# USBtoMIDI.net
KiCad netlist of a schematic drawn in EasyEDA
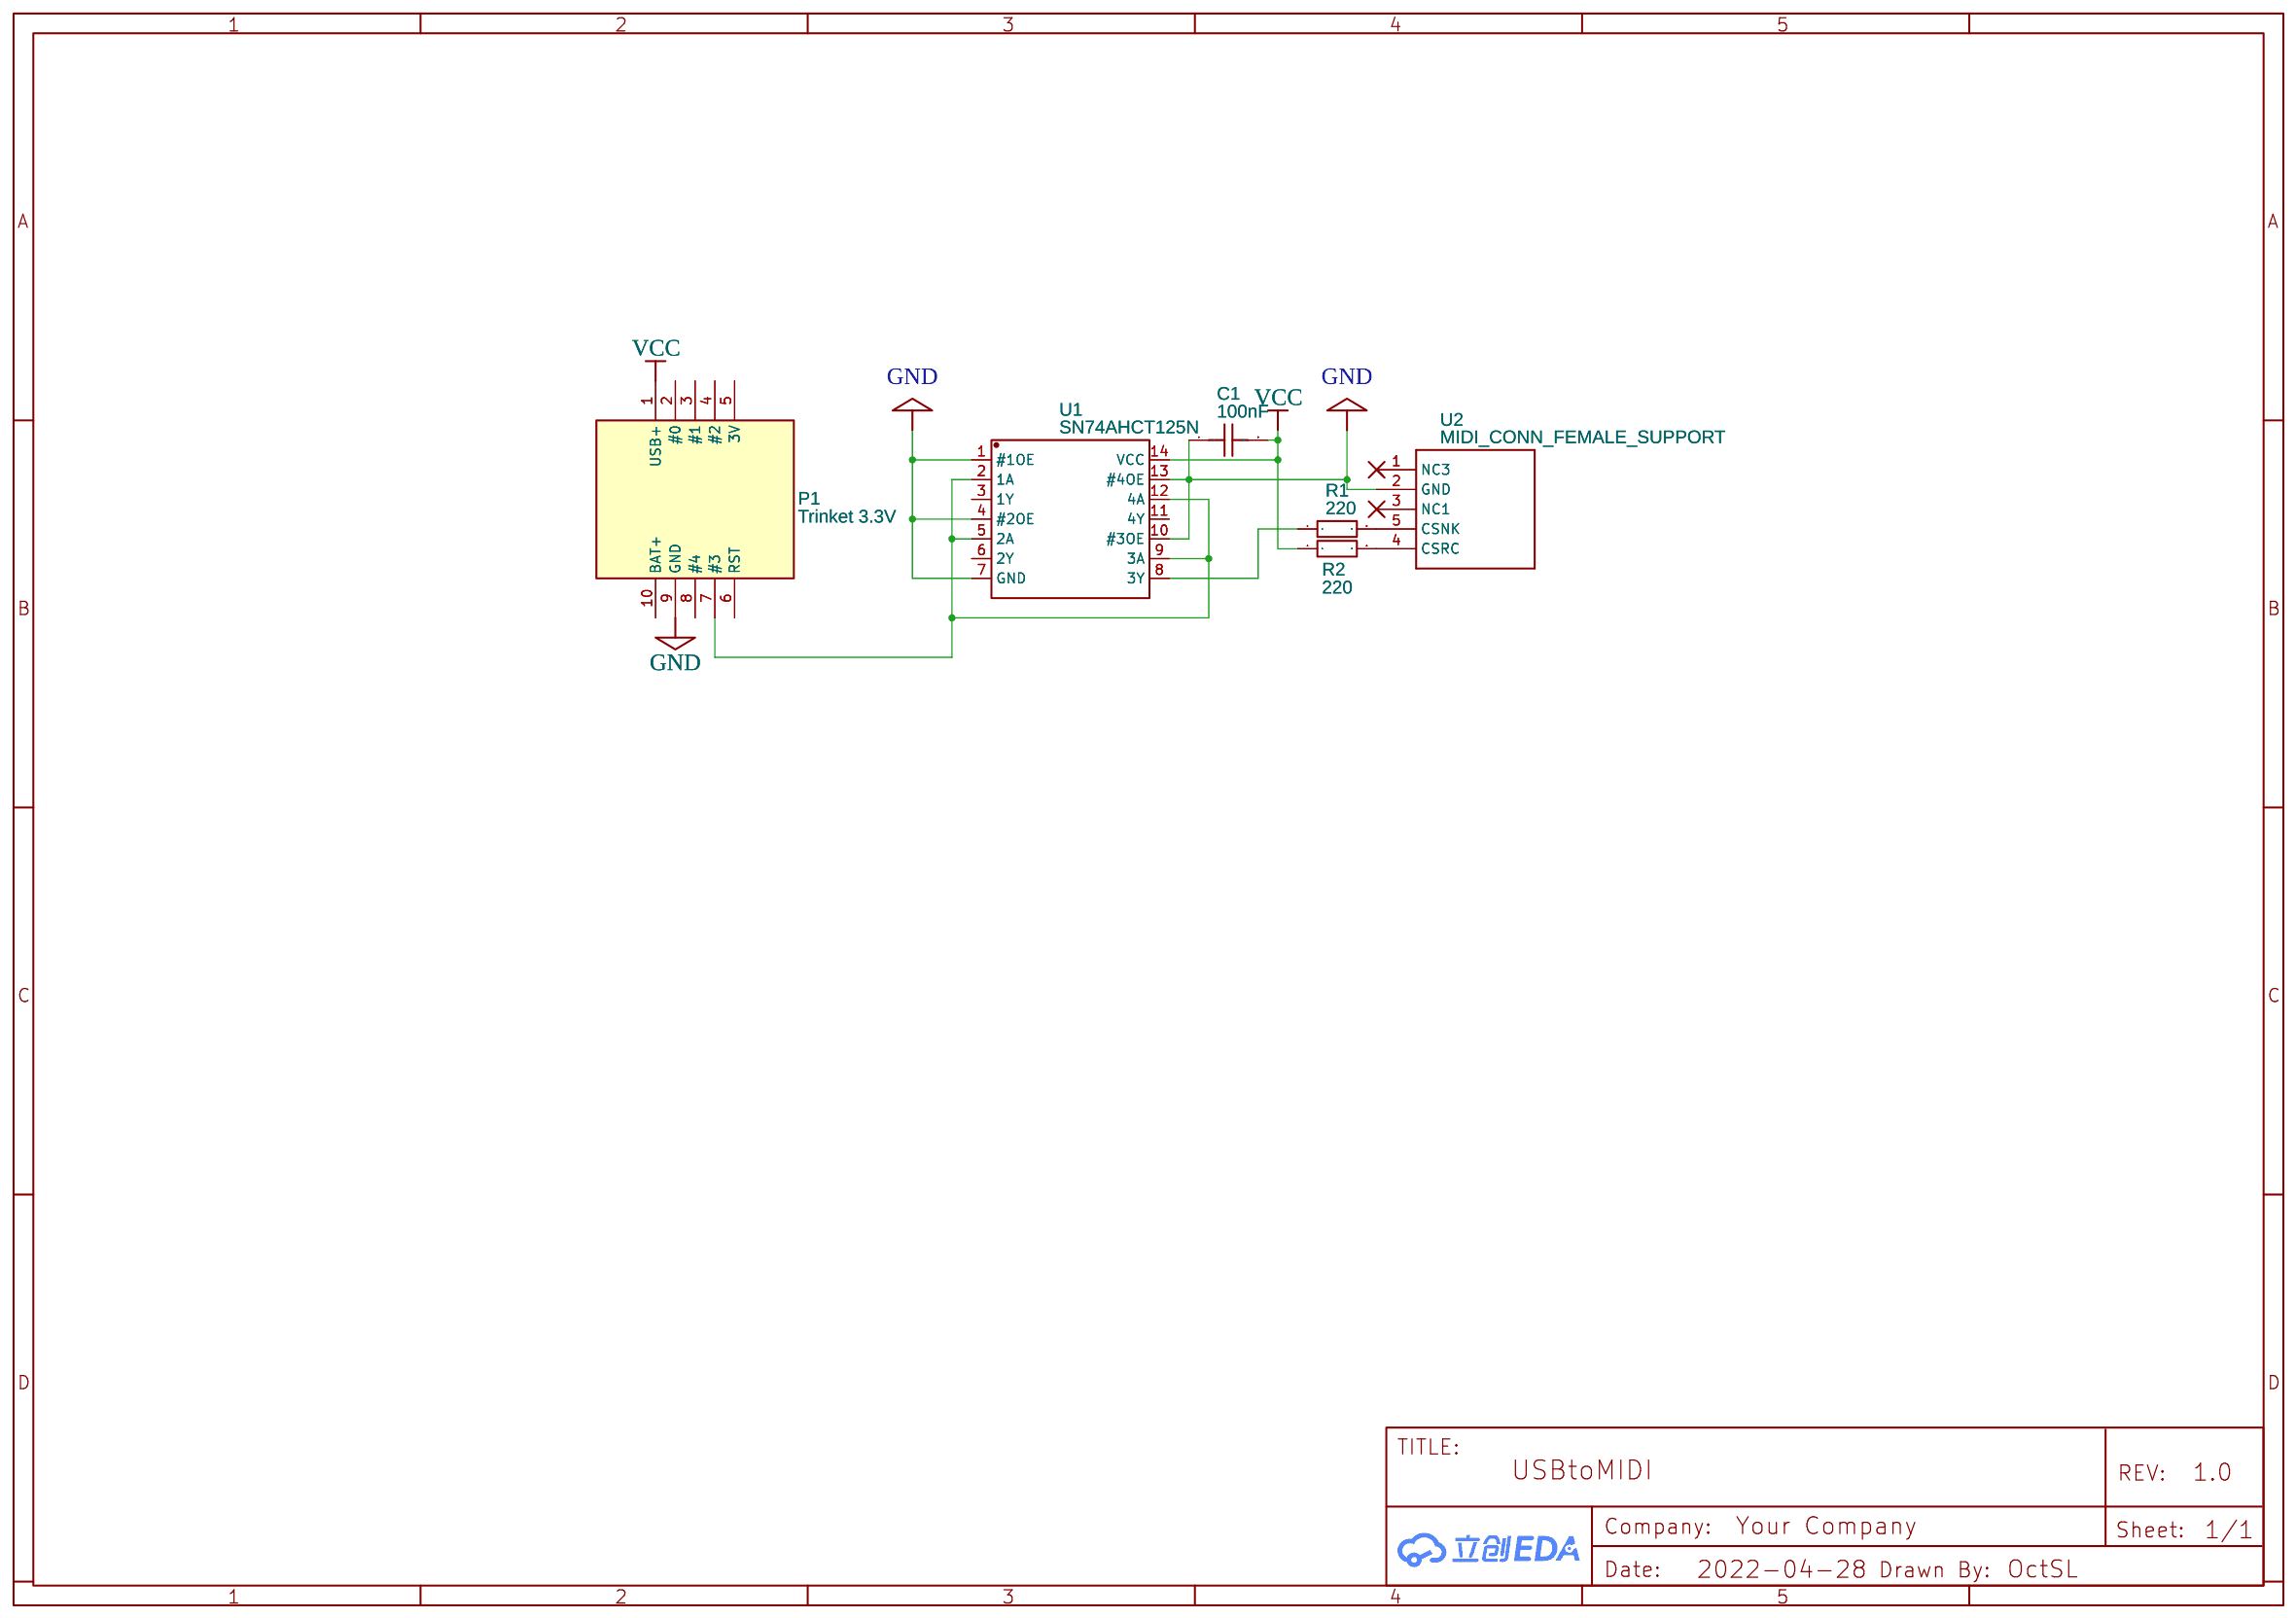
[diagram p0: schematic sheet]

(export (version "E")
  (design (tool "Eeschema 10.0.6"))
  (components
    (comp (ref "C1")
      (value "100nF")
      (fields
        (field (name "BOM_Manufacturer Part") "ACC-B104K500P")
        (field (name "BOM_Supplier Part") "C94703")
      )
      (libsource (lib "") (part "ACC-B104K500P"))
    )
    (comp (ref "P1") (value "Trinket 3.3V") (libsource (lib "") (part "Trinket 3.3V")))
    (comp (ref "R1")
      (value "220")
      (fields (field (name "BOM_Supplier Part") "C122180"))
      (libsource (lib "") (part "RI40-1/4W-1MΩ±5% T"))
    )
    (comp (ref "R2")
      (value "220")
      (fields (field (name "BOM_Supplier Part") "C122180"))
      (libsource (lib "") (part "RI40-1/4W-1MΩ±5% T"))
    )
    (comp (ref "U1")
      (value "SN74AHCT125N")
      (fields (field (name "BOM_Supplier Part") "C354152"))
      (libsource (lib "") (part "SN74AHCT125N"))
    )
    (comp (ref "U2")
      (value "MIDI_CONN_FEMALE_SUPPORT")
      (libsource (lib "") (part "MIDI_CONN_FEMALE_SUPPORT"))
    )
  )
  (nets
    (net (code "1") (name "GND") (class "Default")
      (node (ref "C1") (pin "1") (pinfunction "1_1") (pintype "unspecified"))
      (node (ref "P1") (pin "9") (pinfunction "GND_9") (pintype "unspecified"))
      (node (ref "U1") (pin "1") (pinfunction "#1OE_1") (pintype "unspecified"))
      (node (ref "U1") (pin "10") (pinfunction "#3OE_10") (pintype "unspecified"))
      (node (ref "U1") (pin "13") (pinfunction "#4OE_13") (pintype "unspecified"))
      (node (ref "U1") (pin "4") (pinfunction "#2OE_4") (pintype "unspecified"))
      (node (ref "U1") (pin "7") (pinfunction "GND_7") (pintype "unspecified"))
      (node (ref "U2") (pin "2") (pinfunction "GND_2") (pintype "unspecified"))
    )
    (net (code "2") (name "Net-(P1-#3)") (class "Default")
      (node (ref "P1") (pin "7") (pinfunction "#3_7") (pintype "unspecified"))
      (node (ref "U1") (pin "12") (pinfunction "4A_12") (pintype "unspecified"))
      (node (ref "U1") (pin "2") (pinfunction "1A_2") (pintype "unspecified"))
      (node (ref "U1") (pin "5") (pinfunction "2A_5") (pintype "unspecified"))
      (node (ref "U1") (pin "9") (pinfunction "3A_9") (pintype "unspecified"))
    )
    (net (code "3") (name "Net-(U1-3Y)") (class "Default")
      (node (ref "R1") (pin "1") (pinfunction "1_1") (pintype "unspecified"))
      (node (ref "U1") (pin "8") (pinfunction "3Y_8") (pintype "unspecified"))
    )
    (net (code "4") (name "Net-(U2-CSNK)") (class "Default")
      (node (ref "R1") (pin "2") (pinfunction "2_2") (pintype "unspecified"))
      (node (ref "U2") (pin "5") (pinfunction "CSNK_5") (pintype "unspecified"))
    )
    (net (code "5") (name "Net-(U2-CSRC)") (class "Default")
      (node (ref "R2") (pin "2") (pinfunction "2_2") (pintype "unspecified"))
      (node (ref "U2") (pin "4") (pinfunction "CSRC_4") (pintype "unspecified"))
    )
    (net (code "6") (name "VCC") (class "Default")
      (node (ref "C1") (pin "2") (pinfunction "2_2") (pintype "unspecified"))
      (node (ref "P1") (pin "1") (pinfunction "USB+_1") (pintype "unspecified"))
      (node (ref "R2") (pin "1") (pinfunction "1_1") (pintype "unspecified"))
      (node (ref "U1") (pin "14") (pinfunction "VCC_14") (pintype "unspecified"))
    )
    (net (code "7") (name "unconnected-(P1-#0-Pad2)") (class "Default")
      (node (ref "P1") (pin "2") (pinfunction "#0_2") (pintype "unspecified"))
    )
    (net (code "8") (name "unconnected-(P1-#1-Pad3)") (class "Default")
      (node (ref "P1") (pin "3") (pinfunction "#1_3") (pintype "unspecified"))
    )
    (net (code "9") (name "unconnected-(P1-#2-Pad4)") (class "Default")
      (node (ref "P1") (pin "4") (pinfunction "#2_4") (pintype "unspecified"))
    )
    (net (code "10") (name "unconnected-(P1-#4-Pad8)") (class "Default")
      (node (ref "P1") (pin "8") (pinfunction "#4_8") (pintype "unspecified"))
    )
    (net (code "11") (name "unconnected-(P1-3V-Pad5)") (class "Default")
      (node (ref "P1") (pin "5") (pinfunction "3V_5") (pintype "unspecified"))
    )
    (net (code "12") (name "unconnected-(P1-BAT+-Pad10)") (class "Default")
      (node (ref "P1") (pin "10") (pinfunction "BAT+_10") (pintype "unspecified"))
    )
    (net (code "13") (name "unconnected-(P1-RST-Pad6)") (class "Default")
      (node (ref "P1") (pin "6") (pinfunction "RST_6") (pintype "unspecified"))
    )
    (net (code "14") (name "unconnected-(U1-1Y-Pad3)") (class "Default")
      (node (ref "U1") (pin "3") (pinfunction "1Y_3") (pintype "unspecified"))
    )
    (net (code "15") (name "unconnected-(U1-2Y-Pad6)") (class "Default")
      (node (ref "U1") (pin "6") (pinfunction "2Y_6") (pintype "unspecified"))
    )
    (net (code "16") (name "unconnected-(U1-4Y-Pad11)") (class "Default")
      (node (ref "U1") (pin "11") (pinfunction "4Y_11") (pintype "unspecified"))
    )
    (net (code "17") (name "unconnected-(U2-NC1-Pad3)") (class "Default")
      (node (ref "U2") (pin "3") (pinfunction "NC1_3") (pintype "unspecified"))
    )
    (net (code "18") (name "unconnected-(U2-NC3-Pad1)") (class "Default")
      (node (ref "U2") (pin "1") (pinfunction "NC3_1") (pintype "unspecified"))
    )
  )
)
